# video_board_yis805.net
KiCad netlist of a schematic drawn in EAGLE
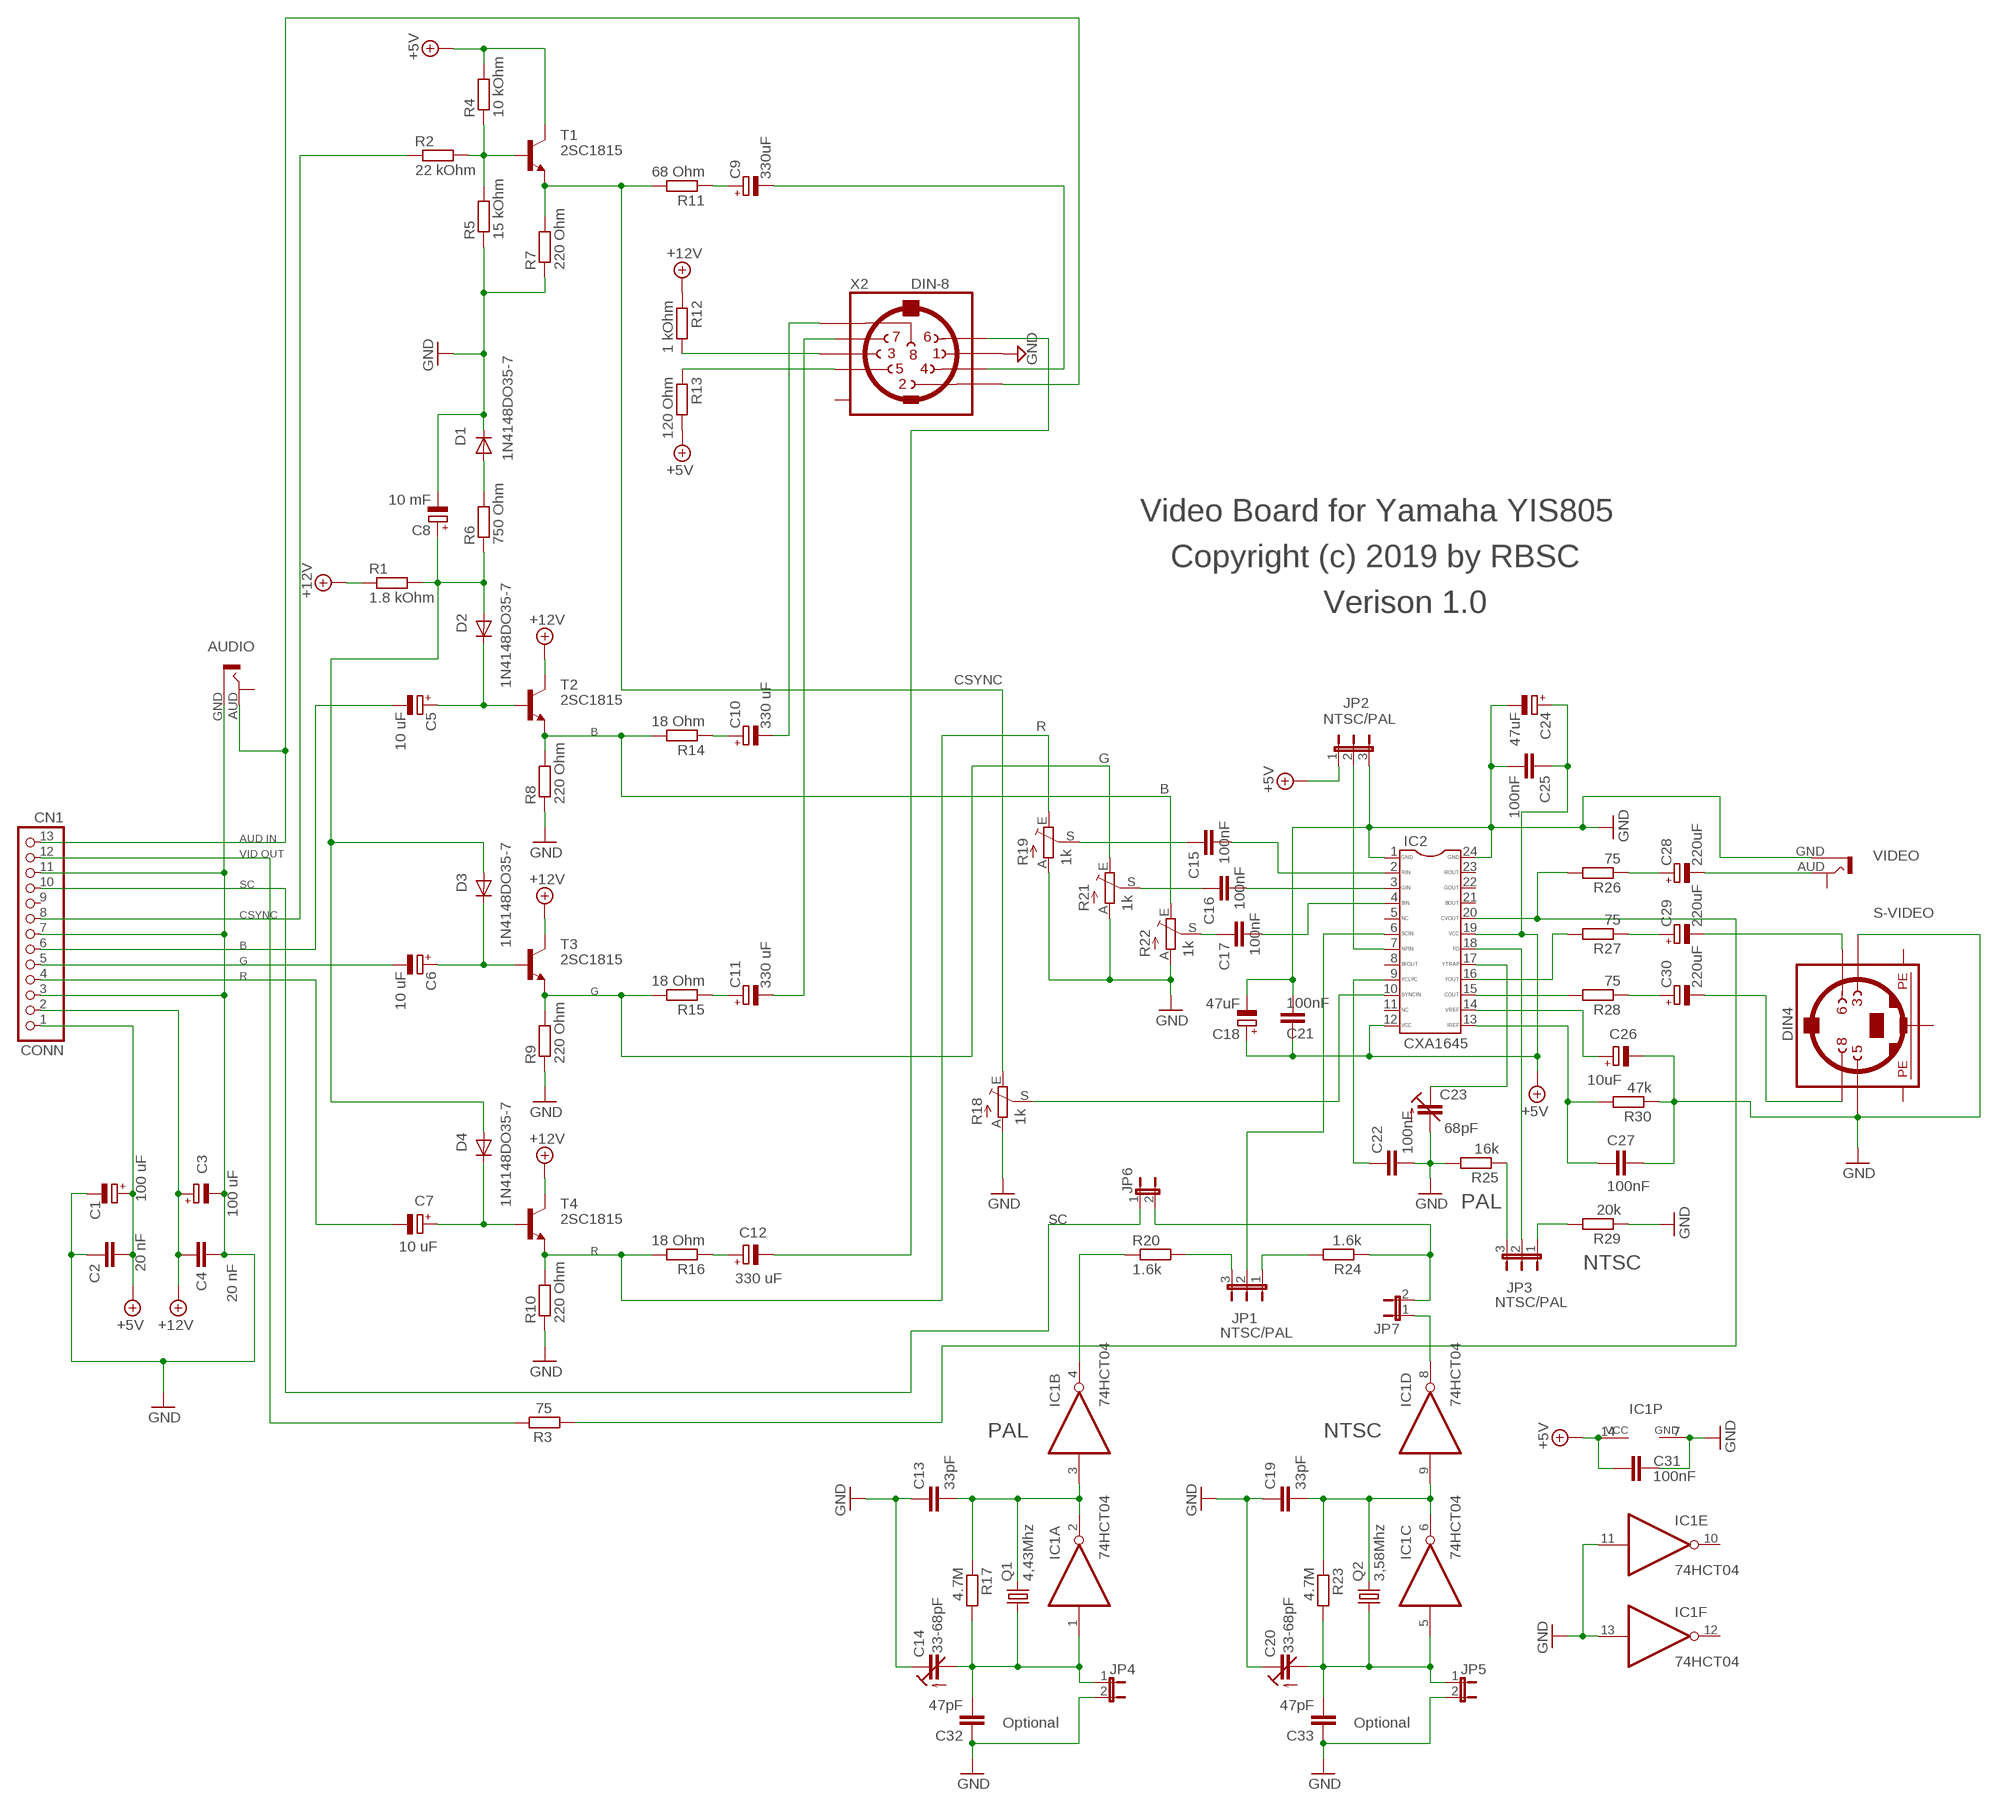
[diagram p0: schematic, sheet 1]

(export (version "E")
  (design (tool "Eeschema 10.0.6"))
  (components
    (comp (ref "AUDIO")
      (value "RCA")
      (footprint "eagle-import:RCA")
      (libsource (lib "eagle-import") (part "RCA"))
    )
    (comp (ref "C1")
      (value "100 uF")
      (footprint "eagle-import:SMC_D")
      (libsource (lib "eagle-import") (part "CPOL-EUSMCD"))
    )
    (comp (ref "C2")
      (value "20 nF")
      (footprint "eagle-import:C0805")
      (libsource (lib "eagle-import") (part "C-EUC0805"))
    )
    (comp (ref "C3")
      (value "100 uF")
      (footprint "eagle-import:SMC_D")
      (libsource (lib "eagle-import") (part "CPOL-EUSMCD"))
    )
    (comp (ref "C4")
      (value "20 nF")
      (footprint "eagle-import:C0805")
      (libsource (lib "eagle-import") (part "C-EUC0805"))
    )
    (comp (ref "C5")
      (value "10 uF")
      (footprint "eagle-import:SMC_B")
      (libsource (lib "eagle-import") (part "CPOL-EUSMCB"))
    )
    (comp (ref "C6")
      (value "10 uF")
      (footprint "eagle-import:SMC_B")
      (libsource (lib "eagle-import") (part "CPOL-EUSMCB"))
    )
    (comp (ref "C7")
      (value "10 uF")
      (footprint "eagle-import:SMC_B")
      (libsource (lib "eagle-import") (part "CPOL-EUSMCB"))
    )
    (comp (ref "C8")
      (value "10 mF")
      (footprint "eagle-import:SMC_B")
      (libsource (lib "eagle-import") (part "CPOL-EUSMCB"))
    )
    (comp (ref "C9")
      (value "330uF")
      (footprint "eagle-import:SMC_D")
      (libsource (lib "eagle-import") (part "CPOL-EUSMCD"))
    )
    (comp (ref "C10")
      (value "330 uF")
      (footprint "eagle-import:SMC_D")
      (libsource (lib "eagle-import") (part "CPOL-EUSMCD"))
    )
    (comp (ref "C11")
      (value "330 uF")
      (footprint "eagle-import:SMC_D")
      (libsource (lib "eagle-import") (part "CPOL-EUSMCD"))
    )
    (comp (ref "C12")
      (value "330 uF")
      (footprint "eagle-import:SMC_D")
      (libsource (lib "eagle-import") (part "CPOL-EUSMCD"))
    )
    (comp (ref "C13")
      (value "33pF")
      (footprint "eagle-import:C0805")
      (libsource (lib "eagle-import") (part "C-EUC0805"))
    )
    (comp (ref "C14")
      (value "33-68pF")
      (footprint "eagle-import:CTRIMTZ03")
      (libsource (lib "eagle-import") (part "C-TRIMMTZ03"))
    )
    (comp (ref "C15")
      (value "100nF")
      (footprint "eagle-import:C0805")
      (libsource (lib "eagle-import") (part "C-EUC0805"))
    )
    (comp (ref "C16")
      (value "100nF")
      (footprint "eagle-import:C0805")
      (libsource (lib "eagle-import") (part "C-EUC0805"))
    )
    (comp (ref "C17")
      (value "100nF")
      (footprint "eagle-import:C0805")
      (libsource (lib "eagle-import") (part "C-EUC0805"))
    )
    (comp (ref "C18")
      (value "47uF")
      (footprint "eagle-import:SMC_B")
      (libsource (lib "eagle-import") (part "CPOL-EUSMCB"))
    )
    (comp (ref "C19")
      (value "33pF")
      (footprint "eagle-import:C0805")
      (libsource (lib "eagle-import") (part "C-EUC0805"))
    )
    (comp (ref "C20")
      (value "33-68pF")
      (footprint "eagle-import:CTRIMTZ03")
      (libsource (lib "eagle-import") (part "C-TRIMMTZ03"))
    )
    (comp (ref "C21")
      (value "100nF")
      (footprint "eagle-import:C0805")
      (libsource (lib "eagle-import") (part "C-EUC0805"))
    )
    (comp (ref "C22")
      (value "100nF")
      (footprint "eagle-import:C0805")
      (libsource (lib "eagle-import") (part "C-EUC0805"))
    )
    (comp (ref "C23")
      (value "68pF")
      (footprint "eagle-import:CTRIMTZ03")
      (libsource (lib "eagle-import") (part "C-TRIMMTZ03"))
    )
    (comp (ref "C24")
      (value "47uF")
      (footprint "eagle-import:SMC_B")
      (libsource (lib "eagle-import") (part "CPOL-EUSMCB"))
    )
    (comp (ref "C25")
      (value "100nF")
      (footprint "eagle-import:C0805")
      (libsource (lib "eagle-import") (part "C-EUC0805"))
    )
    (comp (ref "C26")
      (value "10uF")
      (footprint "eagle-import:SMC_B")
      (libsource (lib "eagle-import") (part "CPOL-EUSMCB"))
    )
    (comp (ref "C27")
      (value "100nF")
      (footprint "eagle-import:C0805")
      (libsource (lib "eagle-import") (part "C-EUC0805"))
    )
    (comp (ref "C28")
      (value "220uF")
      (footprint "eagle-import:SMC_D")
      (libsource (lib "eagle-import") (part "CPOL-EUSMCD"))
    )
    (comp (ref "C29")
      (value "220uF")
      (footprint "eagle-import:SMC_D")
      (libsource (lib "eagle-import") (part "CPOL-EUSMCD"))
    )
    (comp (ref "C30")
      (value "220uF")
      (footprint "eagle-import:SMC_D")
      (libsource (lib "eagle-import") (part "CPOL-EUSMCD"))
    )
    (comp (ref "C31")
      (value "100nF")
      (footprint "eagle-import:C0805")
      (libsource (lib "eagle-import") (part "C-EUC0805"))
    )
    (comp (ref "C32")
      (value "47pF")
      (footprint "eagle-import:C0805")
      (libsource (lib "eagle-import") (part "C-EUC0805"))
    )
    (comp (ref "C33")
      (value "47pF")
      (footprint "eagle-import:C0805")
      (libsource (lib "eagle-import") (part "C-EUC0805"))
    )
    (comp (ref "CONN")
      (value "CN1")
      (footprint "eagle-import:1X13")
      (libsource (lib "eagle-import") (part "PINHD-1X13"))
    )
    (comp (ref "D1")
      (value "1N4148DO35-7")
      (footprint "eagle-import:MINIMELF")
      (libsource (lib "eagle-import") (part "DIODE-MINIMELF"))
    )
    (comp (ref "D2")
      (value "1N4148DO35-7")
      (footprint "eagle-import:MINIMELF")
      (libsource (lib "eagle-import") (part "DIODE-MINIMELF"))
    )
    (comp (ref "D3")
      (value "1N4148DO35-7")
      (footprint "eagle-import:MINIMELF")
      (libsource (lib "eagle-import") (part "DIODE-MINIMELF"))
    )
    (comp (ref "D4")
      (value "1N4148DO35-7")
      (footprint "eagle-import:MINIMELF")
      (libsource (lib "eagle-import") (part "DIODE-MINIMELF"))
    )
    (comp (ref "IC1")
      (value "74HCT04")
      (footprint "eagle-import:SO14")
      (libsource (lib "eagle-import") (part "7404DHCT"))
    )
    (comp (ref "IC2")
      (value "CXA1645")
      (footprint "eagle-import:SOP24")
      (libsource (lib "eagle-import") (part "CXA1645"))
    )
    (comp (ref "JP1")
      (value "NTSC/PAL")
      (footprint "eagle-import:JP2")
      (libsource (lib "eagle-import") (part "JP2E"))
    )
    (comp (ref "JP2")
      (value "NTSC/PAL")
      (footprint "eagle-import:JP2")
      (libsource (lib "eagle-import") (part "JP2E"))
    )
    (comp (ref "JP3")
      (value "NTSC/PAL")
      (footprint "eagle-import:JP2")
      (libsource (lib "eagle-import") (part "JP2E"))
    )
    (comp (ref "JP4")
      (value "JP1E")
      (footprint "eagle-import:JP1")
      (libsource (lib "eagle-import") (part "JP1E"))
    )
    (comp (ref "JP5")
      (value "JP1E")
      (footprint "eagle-import:JP1")
      (libsource (lib "eagle-import") (part "JP1E"))
    )
    (comp (ref "JP6")
      (value "JP1E")
      (footprint "eagle-import:JP1")
      (libsource (lib "eagle-import") (part "JP1E"))
    )
    (comp (ref "JP7")
      (value "JP1E")
      (footprint "eagle-import:JP1")
      (libsource (lib "eagle-import") (part "JP1E"))
    )
    (comp (ref "Q1")
      (value "4,43Mhz")
      (footprint "eagle-import:HC49_S")
      (fields (field (name "MF") "MULTICOMP") (field (name "MPN") "HC49SM-3.6864-30-50-60-16-ATF"))
      (libsource (lib "eagle-import") (part "CRYSTALHC49S"))
    )
    (comp (ref "Q2")
      (value "3,58Mhz")
      (footprint "eagle-import:HC49_S")
      (fields (field (name "MF") "MULTICOMP") (field (name "MPN") "HC49SM-3.6864-30-50-60-16-ATF"))
      (libsource (lib "eagle-import") (part "CRYSTALHC49S"))
    )
    (comp (ref "R1")
      (value "1.8 kOhm")
      (footprint "eagle-import:R0805")
      (libsource (lib "eagle-import") (part "resistor_R-EU_R0805"))
    )
    (comp (ref "R2")
      (value "22 kOhm")
      (footprint "eagle-import:R0805")
      (libsource (lib "eagle-import") (part "resistor_R-EU_R0805"))
    )
    (comp (ref "R3")
      (value "75")
      (footprint "eagle-import:R0805")
      (libsource (lib "eagle-import") (part "R-EU_R0805"))
    )
    (comp (ref "R4")
      (value "10 kOhm")
      (footprint "eagle-import:R0805")
      (libsource (lib "eagle-import") (part "resistor_R-EU_R0805"))
    )
    (comp (ref "R5")
      (value "15 kOhm")
      (footprint "eagle-import:R0805")
      (libsource (lib "eagle-import") (part "resistor_R-EU_R0805"))
    )
    (comp (ref "R6")
      (value "750 Ohm")
      (footprint "eagle-import:R0805")
      (libsource (lib "eagle-import") (part "resistor_R-EU_R0805"))
    )
    (comp (ref "R7")
      (value "220 Ohm")
      (footprint "eagle-import:R0805")
      (libsource (lib "eagle-import") (part "resistor_R-EU_R0805"))
    )
    (comp (ref "R8")
      (value "220 Ohm")
      (footprint "eagle-import:R0805")
      (libsource (lib "eagle-import") (part "resistor_R-EU_R0805"))
    )
    (comp (ref "R9")
      (value "220 Ohm")
      (footprint "eagle-import:R0805")
      (libsource (lib "eagle-import") (part "resistor_R-EU_R0805"))
    )
    (comp (ref "R10")
      (value "220 Ohm")
      (footprint "eagle-import:R0805")
      (libsource (lib "eagle-import") (part "resistor_R-EU_R0805"))
    )
    (comp (ref "R11")
      (value "68 Ohm")
      (footprint "eagle-import:R0805")
      (libsource (lib "eagle-import") (part "resistor_R-EU_R0805"))
    )
    (comp (ref "R12")
      (value "1 kOhm")
      (footprint "eagle-import:R0805")
      (libsource (lib "eagle-import") (part "resistor_R-EU_R0805"))
    )
    (comp (ref "R13")
      (value "120 Ohm")
      (footprint "eagle-import:R0805")
      (libsource (lib "eagle-import") (part "resistor_R-EU_R0805"))
    )
    (comp (ref "R14")
      (value "18 Ohm")
      (footprint "eagle-import:R0805")
      (libsource (lib "eagle-import") (part "resistor_R-EU_R0805"))
    )
    (comp (ref "R15")
      (value "18 Ohm")
      (footprint "eagle-import:R0805")
      (libsource (lib "eagle-import") (part "resistor_R-EU_R0805"))
    )
    (comp (ref "R16")
      (value "18 Ohm")
      (footprint "eagle-import:R0805")
      (libsource (lib "eagle-import") (part "resistor_R-EU_R0805"))
    )
    (comp (ref "R17")
      (value "4.7M")
      (footprint "eagle-import:R0805")
      (libsource (lib "eagle-import") (part "R-EU_R0805"))
    )
    (comp (ref "R18")
      (value "1k")
      (footprint "eagle-import:CA6V")
      (libsource (lib "eagle-import") (part "TRIM_EU-CA6V"))
    )
    (comp (ref "R19")
      (value "1k")
      (footprint "eagle-import:CA6V")
      (libsource (lib "eagle-import") (part "TRIM_EU-CA6V"))
    )
    (comp (ref "R20")
      (value "1.6k")
      (footprint "eagle-import:R0805")
      (libsource (lib "eagle-import") (part "R-EU_R0805"))
    )
    (comp (ref "R21")
      (value "1k")
      (footprint "eagle-import:CA6V")
      (libsource (lib "eagle-import") (part "TRIM_EU-CA6V"))
    )
    (comp (ref "R22")
      (value "1k")
      (footprint "eagle-import:CA6V")
      (libsource (lib "eagle-import") (part "TRIM_EU-CA6V"))
    )
    (comp (ref "R23")
      (value "4.7M")
      (footprint "eagle-import:R0805")
      (libsource (lib "eagle-import") (part "R-EU_R0805"))
    )
    (comp (ref "R24")
      (value "1.6k")
      (footprint "eagle-import:R0805")
      (libsource (lib "eagle-import") (part "R-EU_R0805"))
    )
    (comp (ref "R25")
      (value "16k")
      (footprint "eagle-import:R0805")
      (libsource (lib "eagle-import") (part "R-EU_R0805"))
    )
    (comp (ref "R26")
      (value "75")
      (footprint "eagle-import:R0805")
      (libsource (lib "eagle-import") (part "R-EU_R0805"))
    )
    (comp (ref "R27")
      (value "75")
      (footprint "eagle-import:R0805")
      (libsource (lib "eagle-import") (part "R-EU_R0805"))
    )
    (comp (ref "R28")
      (value "75")
      (footprint "eagle-import:R0805")
      (libsource (lib "eagle-import") (part "R-EU_R0805"))
    )
    (comp (ref "R29")
      (value "20k")
      (footprint "eagle-import:R0805")
      (libsource (lib "eagle-import") (part "R-EU_R0805"))
    )
    (comp (ref "R30")
      (value "47k")
      (footprint "eagle-import:R0805")
      (libsource (lib "eagle-import") (part "R-EU_R0805"))
    )
    (comp (ref "S-VIDEO")
      (value "DIN4")
      (footprint "eagle-import:M_DIN4")
      (libsource (lib "eagle-import") (part "MINI_DIN_4"))
    )
    (comp (ref "T1")
      (value "2SC1815")
      (footprint "eagle-import:TO92-ECB")
      (libsource (lib "eagle-import") (part "2SC1815"))
    )
    (comp (ref "T2")
      (value "2SC1815")
      (footprint "eagle-import:TO92-ECB")
      (libsource (lib "eagle-import") (part "2SC1815"))
    )
    (comp (ref "T3")
      (value "2SC1815")
      (footprint "eagle-import:TO92-ECB")
      (libsource (lib "eagle-import") (part "2SC1815"))
    )
    (comp (ref "T4")
      (value "2SC1815")
      (footprint "eagle-import:TO92-ECB")
      (libsource (lib "eagle-import") (part "2SC1815"))
    )
    (comp (ref "VIDEO")
      (value "RCA")
      (footprint "eagle-import:RCA")
      (libsource (lib "eagle-import") (part "RCA"))
    )
    (comp (ref "X2")
      (value "DIN-8")
      (footprint "eagle-import:DIN8")
      (libsource (lib "eagle-import") (part "DIN-8"))
    )
  )
  (nets
    (net (code "1") (name "+5V") (class "Default")
      (node (ref "C1") (pin "+") (pinfunction "+_+") (pintype "passive"))
      (node (ref "C18") (pin "+") (pinfunction "+_+") (pintype "passive"))
      (node (ref "C2") (pin "1") (pinfunction "1_1") (pintype "passive"))
      (node (ref "C21") (pin "1") (pinfunction "1_1") (pintype "passive"))
      (node (ref "C24") (pin "+") (pinfunction "+_+") (pintype "passive"))
      (node (ref "C25") (pin "1") (pinfunction "1_1") (pintype "passive"))
      (node (ref "C31") (pin "2") (pinfunction "2_2") (pintype "passive"))
      (node (ref "CONN") (pin "1") (pinfunction "1_1") (pintype "passive"))
      (node (ref "IC1") (pin "14") (pinfunction "VCC_14") (pintype "power_in"))
      (node (ref "IC2") (pin "12") (pinfunction "12_12") (pintype "passive"))
      (node (ref "IC2") (pin "19") (pinfunction "19_19") (pintype "passive"))
      (node (ref "JP2") (pin "1") (pinfunction "1_1") (pintype "passive"))
      (node (ref "R13") (pin "2") (pinfunction "2_2") (pintype "passive"))
      (node (ref "R4") (pin "2") (pinfunction "2_2") (pintype "passive"))
      (node (ref "T1") (pin "C") (pinfunction "C_C") (pintype "passive"))
    )
    (net (code "2") (name "+12V") (class "Default")
      (node (ref "C3") (pin "+") (pinfunction "+_+") (pintype "passive"))
      (node (ref "C4") (pin "1") (pinfunction "1_1") (pintype "passive"))
      (node (ref "CONN") (pin "2") (pinfunction "2_2") (pintype "passive"))
      (node (ref "R1") (pin "1") (pinfunction "1_1") (pintype "passive"))
      (node (ref "R12") (pin "1") (pinfunction "1_1") (pintype "passive"))
      (node (ref "T2") (pin "C") (pinfunction "C_C") (pintype "passive"))
      (node (ref "T3") (pin "C") (pinfunction "C_C") (pintype "passive"))
      (node (ref "T4") (pin "C") (pinfunction "C_C") (pintype "passive"))
    )
    (net (code "3") (name "/PE1") (class "Default")
      (node (ref "S-VIDEO") (pin "SH1") (pinfunction "PE1_SH1") (pintype "power_in"))
    )
    (net (code "4") (name "/PE2") (class "Default")
      (node (ref "S-VIDEO") (pin "SH2") (pinfunction "PE2_SH2") (pintype "power_in"))
    )
    (net (code "5") (name "/PE3") (class "Default")
      (node (ref "S-VIDEO") (pin "SH3") (pinfunction "PE3_SH3") (pintype "power_in"))
    )
    (net (code "6") (name "/SC") (class "Default")
      (node (ref "CONN") (pin "10") (pinfunction "10_10") (pintype "passive"))
      (node (ref "JP6") (pin "1") (pinfunction "1_1") (pintype "passive"))
    )
    (net (code "7") (name "GND") (class "Default")
      (node (ref "AUDIO") (pin "GND") (pinfunction "GND1_GND") (pintype "passive"))
      (node (ref "C1") (pin "-") (pinfunction "-_-") (pintype "passive"))
      (node (ref "C13") (pin "1") (pinfunction "1_1") (pintype "passive"))
      (node (ref "C14") (pin "1") (pinfunction "E_1") (pintype "passive"))
      (node (ref "C18") (pin "-") (pinfunction "-_-") (pintype "passive"))
      (node (ref "C19") (pin "1") (pinfunction "1_1") (pintype "passive"))
      (node (ref "C2") (pin "2") (pinfunction "2_2") (pintype "passive"))
      (node (ref "C20") (pin "1") (pinfunction "E_1") (pintype "passive"))
      (node (ref "C21") (pin "2") (pinfunction "2_2") (pintype "passive"))
      (node (ref "C22") (pin "2") (pinfunction "2_2") (pintype "passive"))
      (node (ref "C23") (pin "2") (pinfunction "A_2") (pintype "passive"))
      (node (ref "C24") (pin "-") (pinfunction "-_-") (pintype "passive"))
      (node (ref "C25") (pin "2") (pinfunction "2_2") (pintype "passive"))
      (node (ref "C26") (pin "-") (pinfunction "-_-") (pintype "passive"))
      (node (ref "C27") (pin "2") (pinfunction "2_2") (pintype "passive"))
      (node (ref "C3") (pin "-") (pinfunction "-_-") (pintype "passive"))
      (node (ref "C31") (pin "1") (pinfunction "1_1") (pintype "passive"))
      (node (ref "C32") (pin "1") (pinfunction "1_1") (pintype "passive"))
      (node (ref "C33") (pin "1") (pinfunction "1_1") (pintype "passive"))
      (node (ref "C4") (pin "2") (pinfunction "2_2") (pintype "passive"))
      (node (ref "C8") (pin "-") (pinfunction "-_-") (pintype "passive"))
      (node (ref "CONN") (pin "11") (pinfunction "11_11") (pintype "passive"))
      (node (ref "CONN") (pin "3") (pinfunction "3_3") (pintype "passive"))
      (node (ref "CONN") (pin "7") (pinfunction "7_7") (pintype "passive"))
      (node (ref "D1") (pin "C") (pinfunction "C_C") (pintype "passive"))
      (node (ref "IC1") (pin "11") (pinfunction "I_11") (pintype "input"))
      (node (ref "IC1") (pin "13") (pinfunction "I_13") (pintype "input"))
      (node (ref "IC1") (pin "7") (pinfunction "GND_7") (pintype "power_in"))
      (node (ref "IC2") (pin "1") (pinfunction "1_1") (pintype "passive"))
      (node (ref "IC2") (pin "24") (pinfunction "24_24") (pintype "passive"))
      (node (ref "JP2") (pin "3") (pinfunction "3_3") (pintype "passive"))
      (node (ref "JP4") (pin "2") (pinfunction "2_2") (pintype "passive"))
      (node (ref "JP5") (pin "2") (pinfunction "2_2") (pintype "passive"))
      (node (ref "R10") (pin "1") (pinfunction "1_1") (pintype "passive"))
      (node (ref "R18") (pin "A") (pinfunction "A_A") (pintype "passive"))
      (node (ref "R19") (pin "A") (pinfunction "A_A") (pintype "passive"))
      (node (ref "R21") (pin "A") (pinfunction "A_A") (pintype "passive"))
      (node (ref "R22") (pin "A") (pinfunction "A_A") (pintype "passive"))
      (node (ref "R25") (pin "2") (pinfunction "2_2") (pintype "passive"))
      (node (ref "R29") (pin "1") (pinfunction "1_1") (pintype "passive"))
      (node (ref "R30") (pin "1") (pinfunction "1_1") (pintype "passive"))
      (node (ref "R5") (pin "1") (pinfunction "1_1") (pintype "passive"))
      (node (ref "R7") (pin "1") (pinfunction "1_1") (pintype "passive"))
      (node (ref "R8") (pin "1") (pinfunction "1_1") (pintype "passive"))
      (node (ref "R9") (pin "1") (pinfunction "1_1") (pintype "passive"))
      (node (ref "S-VIDEO") (pin "3") (pinfunction "3_3") (pintype "passive"))
      (node (ref "S-VIDEO") (pin "5") (pinfunction "5_5") (pintype "passive"))
      (node (ref "VIDEO") (pin "GND") (pinfunction "GND1_GND") (pintype "passive"))
      (node (ref "X2") (pin "1") (pinfunction "1_1") (pintype "passive"))
    )
    (net (code "8") (name "Net-(AUDIO-PadAUD)") (class "Default")
      (node (ref "AUDIO") (pin "AUD") (pinfunction "AUD_AUD") (pintype "passive"))
      (node (ref "CONN") (pin "13") (pinfunction "13_13") (pintype "passive"))
      (node (ref "X2") (pin "2") (pinfunction "2_2") (pintype "passive"))
    )
    (net (code "9") (name "Net-(C5-Pad+)") (class "Default")
      (node (ref "C5") (pin "+") (pinfunction "+_+") (pintype "passive"))
      (node (ref "D2") (pin "C") (pinfunction "C_C") (pintype "passive"))
      (node (ref "T2") (pin "B") (pinfunction "B_B") (pintype "passive"))
    )
    (net (code "10") (name "Net-(C5-Pad-)") (class "Default")
      (node (ref "C5") (pin "-") (pinfunction "-_-") (pintype "passive"))
      (node (ref "CONN") (pin "6") (pinfunction "6_6") (pintype "passive"))
    )
    (net (code "11") (name "Net-(C6-Pad+)") (class "Default")
      (node (ref "C6") (pin "+") (pinfunction "+_+") (pintype "passive"))
      (node (ref "D3") (pin "C") (pinfunction "C_C") (pintype "passive"))
      (node (ref "T3") (pin "B") (pinfunction "B_B") (pintype "passive"))
    )
    (net (code "12") (name "Net-(C6-Pad-)") (class "Default")
      (node (ref "C6") (pin "-") (pinfunction "-_-") (pintype "passive"))
      (node (ref "CONN") (pin "5") (pinfunction "5_5") (pintype "passive"))
    )
    (net (code "13") (name "Net-(C7-Pad+)") (class "Default")
      (node (ref "C7") (pin "+") (pinfunction "+_+") (pintype "passive"))
      (node (ref "D4") (pin "C") (pinfunction "C_C") (pintype "passive"))
      (node (ref "T4") (pin "B") (pinfunction "B_B") (pintype "passive"))
    )
    (net (code "14") (name "Net-(C7-Pad-)") (class "Default")
      (node (ref "C7") (pin "-") (pinfunction "-_-") (pintype "passive"))
      (node (ref "CONN") (pin "4") (pinfunction "4_4") (pintype "passive"))
    )
    (net (code "15") (name "Net-(C8-Pad+)") (class "Default")
      (node (ref "C8") (pin "+") (pinfunction "+_+") (pintype "passive"))
      (node (ref "D2") (pin "A") (pinfunction "A_A") (pintype "passive"))
      (node (ref "D3") (pin "A") (pinfunction "A_A") (pintype "passive"))
      (node (ref "D4") (pin "A") (pinfunction "A_A") (pintype "passive"))
      (node (ref "R1") (pin "2") (pinfunction "2_2") (pintype "passive"))
      (node (ref "R6") (pin "1") (pinfunction "1_1") (pintype "passive"))
    )
    (net (code "16") (name "Net-(C9-Pad+)") (class "Default")
      (node (ref "C9") (pin "+") (pinfunction "+_+") (pintype "passive"))
      (node (ref "R11") (pin "1") (pinfunction "1_1") (pintype "passive"))
    )
    (net (code "17") (name "Net-(C9-Pad-)") (class "Default")
      (node (ref "C9") (pin "-") (pinfunction "-_-") (pintype "passive"))
      (node (ref "X2") (pin "4") (pinfunction "4_4") (pintype "passive"))
    )
    (net (code "18") (name "Net-(C10-Pad+)") (class "Default")
      (node (ref "C10") (pin "+") (pinfunction "+_+") (pintype "passive"))
      (node (ref "R14") (pin "1") (pinfunction "1_1") (pintype "passive"))
    )
    (net (code "19") (name "Net-(C10-Pad-)") (class "Default")
      (node (ref "C10") (pin "-") (pinfunction "-_-") (pintype "passive"))
      (node (ref "X2") (pin "8") (pinfunction "8_8") (pintype "passive"))
    )
    (net (code "20") (name "Net-(C11-Pad+)") (class "Default")
      (node (ref "C11") (pin "+") (pinfunction "+_+") (pintype "passive"))
      (node (ref "R15") (pin "1") (pinfunction "1_1") (pintype "passive"))
    )
    (net (code "21") (name "Net-(C11-Pad-)") (class "Default")
      (node (ref "C11") (pin "-") (pinfunction "-_-") (pintype "passive"))
      (node (ref "X2") (pin "7") (pinfunction "7_7") (pintype "passive"))
    )
    (net (code "22") (name "Net-(C12-Pad+)") (class "Default")
      (node (ref "C12") (pin "+") (pinfunction "+_+") (pintype "passive"))
      (node (ref "R16") (pin "1") (pinfunction "1_1") (pintype "passive"))
    )
    (net (code "23") (name "Net-(C12-Pad-)") (class "Default")
      (node (ref "C12") (pin "-") (pinfunction "-_-") (pintype "passive"))
      (node (ref "X2") (pin "6") (pinfunction "6_6") (pintype "passive"))
    )
    (net (code "24") (name "Net-(C14-A)") (class "Default")
      (node (ref "C14") (pin "2") (pinfunction "A_2") (pintype "passive"))
      (node (ref "C32") (pin "2") (pinfunction "2_2") (pintype "passive"))
      (node (ref "IC1") (pin "1") (pinfunction "I_1") (pintype "input"))
      (node (ref "JP4") (pin "1") (pinfunction "1_1") (pintype "passive"))
      (node (ref "Q1") (pin "1") (pinfunction "1_1") (pintype "passive"))
      (node (ref "R17") (pin "2") (pinfunction "2_2") (pintype "passive"))
    )
    (net (code "25") (name "Net-(C15-Pad1)") (class "Default")
      (node (ref "C15") (pin "1") (pinfunction "1_1") (pintype "passive"))
      (node (ref "R19") (pin "S") (pinfunction "S_S") (pintype "passive"))
    )
    (net (code "26") (name "Net-(C15-Pad2)") (class "Default")
      (node (ref "C15") (pin "2") (pinfunction "2_2") (pintype "passive"))
      (node (ref "IC2") (pin "2") (pinfunction "2_2") (pintype "passive"))
    )
    (net (code "27") (name "Net-(C16-Pad1)") (class "Default")
      (node (ref "C16") (pin "1") (pinfunction "1_1") (pintype "passive"))
      (node (ref "R21") (pin "S") (pinfunction "S_S") (pintype "passive"))
    )
    (net (code "28") (name "Net-(C16-Pad2)") (class "Default")
      (node (ref "C16") (pin "2") (pinfunction "2_2") (pintype "passive"))
      (node (ref "IC2") (pin "3") (pinfunction "3_3") (pintype "passive"))
    )
    (net (code "29") (name "Net-(C17-Pad1)") (class "Default")
      (node (ref "C17") (pin "1") (pinfunction "1_1") (pintype "passive"))
      (node (ref "R22") (pin "S") (pinfunction "S_S") (pintype "passive"))
    )
    (net (code "30") (name "Net-(C17-Pad2)") (class "Default")
      (node (ref "C17") (pin "2") (pinfunction "2_2") (pintype "passive"))
      (node (ref "IC2") (pin "4") (pinfunction "4_4") (pintype "passive"))
    )
    (net (code "31") (name "Net-(C20-A)") (class "Default")
      (node (ref "C20") (pin "2") (pinfunction "A_2") (pintype "passive"))
      (node (ref "C33") (pin "2") (pinfunction "2_2") (pintype "passive"))
      (node (ref "IC1") (pin "5") (pinfunction "I_5") (pintype "input"))
      (node (ref "JP5") (pin "1") (pinfunction "1_1") (pintype "passive"))
      (node (ref "Q2") (pin "1") (pinfunction "1_1") (pintype "passive"))
      (node (ref "R23") (pin "2") (pinfunction "2_2") (pintype "passive"))
    )
    (net (code "32") (name "Net-(C22-Pad1)") (class "Default")
      (node (ref "C22") (pin "1") (pinfunction "1_1") (pintype "passive"))
      (node (ref "IC2") (pin "9") (pinfunction "9_9") (pintype "passive"))
    )
    (net (code "33") (name "Net-(C23-E)") (class "Default")
      (node (ref "C23") (pin "1") (pinfunction "E_1") (pintype "passive"))
      (node (ref "IC2") (pin "17") (pinfunction "17_17") (pintype "passive"))
    )
    (net (code "34") (name "Net-(C26-Pad+)") (class "Default")
      (node (ref "C26") (pin "+") (pinfunction "+_+") (pintype "passive"))
      (node (ref "IC2") (pin "14") (pinfunction "14_14") (pintype "passive"))
    )
    (net (code "35") (name "Net-(C27-Pad1)") (class "Default")
      (node (ref "C27") (pin "1") (pinfunction "1_1") (pintype "passive"))
      (node (ref "IC2") (pin "13") (pinfunction "13_13") (pintype "passive"))
      (node (ref "R30") (pin "2") (pinfunction "2_2") (pintype "passive"))
    )
    (net (code "36") (name "Net-(C28-Pad+)") (class "Default")
      (node (ref "C28") (pin "+") (pinfunction "+_+") (pintype "passive"))
      (node (ref "R26") (pin "1") (pinfunction "1_1") (pintype "passive"))
    )
    (net (code "37") (name "Net-(C28-Pad-)") (class "Default")
      (node (ref "C28") (pin "-") (pinfunction "-_-") (pintype "passive"))
      (node (ref "VIDEO") (pin "AUD") (pinfunction "AUD_AUD") (pintype "passive"))
    )
    (net (code "38") (name "Net-(C29-Pad+)") (class "Default")
      (node (ref "C29") (pin "+") (pinfunction "+_+") (pintype "passive"))
      (node (ref "R27") (pin "1") (pinfunction "1_1") (pintype "passive"))
    )
    (net (code "39") (name "Net-(C29-Pad-)") (class "Default")
      (node (ref "C29") (pin "-") (pinfunction "-_-") (pintype "passive"))
      (node (ref "S-VIDEO") (pin "6") (pinfunction "6_6") (pintype "passive"))
    )
    (net (code "40") (name "Net-(C30-Pad+)") (class "Default")
      (node (ref "C30") (pin "+") (pinfunction "+_+") (pintype "passive"))
      (node (ref "R28") (pin "1") (pinfunction "1_1") (pintype "passive"))
    )
    (net (code "41") (name "Net-(C30-Pad-)") (class "Default")
      (node (ref "C30") (pin "-") (pinfunction "-_-") (pintype "passive"))
      (node (ref "S-VIDEO") (pin "8") (pinfunction "8_8") (pintype "passive"))
    )
    (net (code "42") (name "Net-(CONN-Pad8)") (class "Default")
      (node (ref "CONN") (pin "8") (pinfunction "8_8") (pintype "passive"))
      (node (ref "R2") (pin "1") (pinfunction "1_1") (pintype "passive"))
    )
    (net (code "43") (name "Net-(CONN-Pad12)") (class "Default")
      (node (ref "CONN") (pin "12") (pinfunction "12_12") (pintype "passive"))
      (node (ref "R3") (pin "2") (pinfunction "2_2") (pintype "passive"))
    )
    (net (code "44") (name "Net-(D1-PadA)") (class "Default")
      (node (ref "D1") (pin "A") (pinfunction "A_A") (pintype "passive"))
      (node (ref "R6") (pin "2") (pinfunction "2_2") (pintype "passive"))
    )
    (net (code "45") (name "Net-(IC1A-O)") (class "Default")
      (node (ref "C13") (pin "2") (pinfunction "2_2") (pintype "passive"))
      (node (ref "IC1") (pin "2") (pinfunction "O_2") (pintype "output"))
      (node (ref "IC1") (pin "3") (pinfunction "I_3") (pintype "input"))
      (node (ref "Q1") (pin "2") (pinfunction "2_2") (pintype "passive"))
      (node (ref "R17") (pin "1") (pinfunction "1_1") (pintype "passive"))
    )
    (net (code "46") (name "Net-(IC1B-O)") (class "Default")
      (node (ref "IC1") (pin "4") (pinfunction "O_4") (pintype "output"))
      (node (ref "R20") (pin "1") (pinfunction "1_1") (pintype "passive"))
    )
    (net (code "47") (name "Net-(IC1C-O)") (class "Default")
      (node (ref "C19") (pin "2") (pinfunction "2_2") (pintype "passive"))
      (node (ref "IC1") (pin "6") (pinfunction "O_6") (pintype "output"))
      (node (ref "IC1") (pin "9") (pinfunction "I_9") (pintype "input"))
      (node (ref "Q2") (pin "2") (pinfunction "2_2") (pintype "passive"))
      (node (ref "R23") (pin "1") (pinfunction "1_1") (pintype "passive"))
    )
    (net (code "48") (name "Net-(IC1D-O)") (class "Default")
      (node (ref "IC1") (pin "8") (pinfunction "O_8") (pintype "output"))
      (node (ref "JP7") (pin "1") (pinfunction "1_1") (pintype "passive"))
    )
    (net (code "49") (name "Net-(IC2-Pad6)") (class "Default")
      (node (ref "IC2") (pin "6") (pinfunction "6_6") (pintype "passive"))
      (node (ref "JP1") (pin "2") (pinfunction "2_2") (pintype "passive"))
    )
    (net (code "50") (name "Net-(IC2-Pad7)") (class "Default")
      (node (ref "IC2") (pin "7") (pinfunction "7_7") (pintype "passive"))
      (node (ref "JP2") (pin "2") (pinfunction "2_2") (pintype "passive"))
    )
    (net (code "51") (name "Net-(IC2-Pad10)") (class "Default")
      (node (ref "IC2") (pin "10") (pinfunction "10_10") (pintype "passive"))
      (node (ref "R18") (pin "S") (pinfunction "S_S") (pintype "passive"))
    )
    (net (code "52") (name "Net-(IC2-Pad15)") (class "Default")
      (node (ref "IC2") (pin "15") (pinfunction "15_15") (pintype "passive"))
      (node (ref "R28") (pin "2") (pinfunction "2_2") (pintype "passive"))
    )
    (net (code "53") (name "Net-(IC2-Pad16)") (class "Default")
      (node (ref "IC2") (pin "16") (pinfunction "16_16") (pintype "passive"))
      (node (ref "R27") (pin "2") (pinfunction "2_2") (pintype "passive"))
    )
    (net (code "54") (name "Net-(IC2-Pad18)") (class "Default")
      (node (ref "IC2") (pin "18") (pinfunction "18_18") (pintype "passive"))
      (node (ref "JP3") (pin "2") (pinfunction "2_2") (pintype "passive"))
    )
    (net (code "55") (name "Net-(IC2-Pad20)") (class "Default")
      (node (ref "IC2") (pin "20") (pinfunction "20_20") (pintype "passive"))
      (node (ref "R26") (pin "2") (pinfunction "2_2") (pintype "passive"))
      (node (ref "R3") (pin "1") (pinfunction "1_1") (pintype "passive"))
    )
    (net (code "56") (name "Net-(JP1-Pad1)") (class "Default")
      (node (ref "JP1") (pin "1") (pinfunction "1_1") (pintype "passive"))
      (node (ref "R24") (pin "2") (pinfunction "2_2") (pintype "passive"))
    )
    (net (code "57") (name "Net-(JP1-Pad3)") (class "Default")
      (node (ref "JP1") (pin "3") (pinfunction "3_3") (pintype "passive"))
      (node (ref "R20") (pin "2") (pinfunction "2_2") (pintype "passive"))
    )
    (net (code "58") (name "Net-(JP3-Pad1)") (class "Default")
      (node (ref "JP3") (pin "1") (pinfunction "1_1") (pintype "passive"))
      (node (ref "R29") (pin "2") (pinfunction "2_2") (pintype "passive"))
    )
    (net (code "59") (name "Net-(JP3-Pad3)") (class "Default")
      (node (ref "JP3") (pin "3") (pinfunction "3_3") (pintype "passive"))
      (node (ref "R25") (pin "1") (pinfunction "1_1") (pintype "passive"))
    )
    (net (code "60") (name "Net-(JP6-Pad2)") (class "Default")
      (node (ref "JP6") (pin "2") (pinfunction "2_2") (pintype "passive"))
      (node (ref "JP7") (pin "2") (pinfunction "2_2") (pintype "passive"))
      (node (ref "R24") (pin "1") (pinfunction "1_1") (pintype "passive"))
    )
    (net (code "61") (name "Net-(R2-Pad2)") (class "Default")
      (node (ref "R2") (pin "2") (pinfunction "2_2") (pintype "passive"))
      (node (ref "R4") (pin "1") (pinfunction "1_1") (pintype "passive"))
      (node (ref "R5") (pin "2") (pinfunction "2_2") (pintype "passive"))
      (node (ref "T1") (pin "B") (pinfunction "B_B") (pintype "passive"))
    )
    (net (code "62") (name "Net-(R10-Pad2)") (class "Default")
      (node (ref "R10") (pin "2") (pinfunction "2_2") (pintype "passive"))
      (node (ref "R16") (pin "2") (pinfunction "2_2") (pintype "passive"))
      (node (ref "R19") (pin "E") (pinfunction "E_E") (pintype "passive"))
      (node (ref "T4") (pin "E") (pinfunction "E_E") (pintype "passive"))
    )
    (net (code "63") (name "Net-(R11-Pad2)") (class "Default")
      (node (ref "R11") (pin "2") (pinfunction "2_2") (pintype "passive"))
      (node (ref "R18") (pin "E") (pinfunction "E_E") (pintype "passive"))
      (node (ref "R7") (pin "2") (pinfunction "2_2") (pintype "passive"))
      (node (ref "T1") (pin "E") (pinfunction "E_E") (pintype "passive"))
    )
    (net (code "64") (name "Net-(R12-Pad2)") (class "Default")
      (node (ref "R12") (pin "2") (pinfunction "2_2") (pintype "passive"))
      (node (ref "X2") (pin "3") (pinfunction "3_3") (pintype "passive"))
    )
    (net (code "65") (name "Net-(R13-Pad1)") (class "Default")
      (node (ref "R13") (pin "1") (pinfunction "1_1") (pintype "passive"))
      (node (ref "X2") (pin "5") (pinfunction "5_5") (pintype "passive"))
    )
    (net (code "66") (name "Net-(R14-Pad2)") (class "Default")
      (node (ref "R14") (pin "2") (pinfunction "2_2") (pintype "passive"))
      (node (ref "R22") (pin "E") (pinfunction "E_E") (pintype "passive"))
      (node (ref "R8") (pin "2") (pinfunction "2_2") (pintype "passive"))
      (node (ref "T2") (pin "E") (pinfunction "E_E") (pintype "passive"))
    )
    (net (code "67") (name "Net-(R15-Pad2)") (class "Default")
      (node (ref "R15") (pin "2") (pinfunction "2_2") (pintype "passive"))
      (node (ref "R21") (pin "E") (pinfunction "E_E") (pintype "passive"))
      (node (ref "R9") (pin "2") (pinfunction "2_2") (pintype "passive"))
      (node (ref "T3") (pin "E") (pinfunction "E_E") (pintype "passive"))
    )
    (net (code "68") (name "unconnected-(AUDIO-PadAUD1)") (class "Default")
      (node (ref "AUDIO") (pin "AUD1") (pinfunction "AUD1_AUD1") (pintype "passive"))
    )
    (net (code "69") (name "unconnected-(CONN-Pad9)") (class "Default")
      (node (ref "CONN") (pin "9") (pinfunction "9_9") (pintype "passive"))
    )
    (net (code "70") (name "unconnected-(IC1E-O-Pad10)") (class "Default")
      (node (ref "IC1") (pin "10") (pinfunction "O_10") (pintype "output"))
    )
    (net (code "71") (name "unconnected-(IC1F-O-Pad12)") (class "Default")
      (node (ref "IC1") (pin "12") (pinfunction "O_12") (pintype "output"))
    )
    (net (code "72") (name "unconnected-(IC2-Pad5)") (class "Default")
      (node (ref "IC2") (pin "5") (pinfunction "5_5") (pintype "passive"))
    )
    (net (code "73") (name "unconnected-(IC2-Pad8)") (class "Default")
      (node (ref "IC2") (pin "8") (pinfunction "8_8") (pintype "passive"))
    )
    (net (code "74") (name "unconnected-(IC2-Pad11)") (class "Default")
      (node (ref "IC2") (pin "11") (pinfunction "11_11") (pintype "passive"))
    )
    (net (code "75") (name "unconnected-(IC2-Pad21)") (class "Default")
      (node (ref "IC2") (pin "21") (pinfunction "21_21") (pintype "passive"))
    )
    (net (code "76") (name "unconnected-(IC2-Pad22)") (class "Default")
      (node (ref "IC2") (pin "22") (pinfunction "22_22") (pintype "passive"))
    )
    (net (code "77") (name "unconnected-(IC2-Pad23)") (class "Default")
      (node (ref "IC2") (pin "23") (pinfunction "23_23") (pintype "passive"))
    )
    (net (code "78") (name "unconnected-(VIDEO-PadAUD1)") (class "Default")
      (node (ref "VIDEO") (pin "AUD1") (pinfunction "AUD1_AUD1") (pintype "passive"))
    )
    (net (code "79") (name "unconnected-(X2-PadGND)") (class "Default")
      (node (ref "X2") (pin "GND") (pinfunction "GND_GND") (pintype "no_connect"))
    )
  )
)
